# DIPSY_UL1K16_LED5.net
KiCad netlist of a schematic drawn in Altium Designer
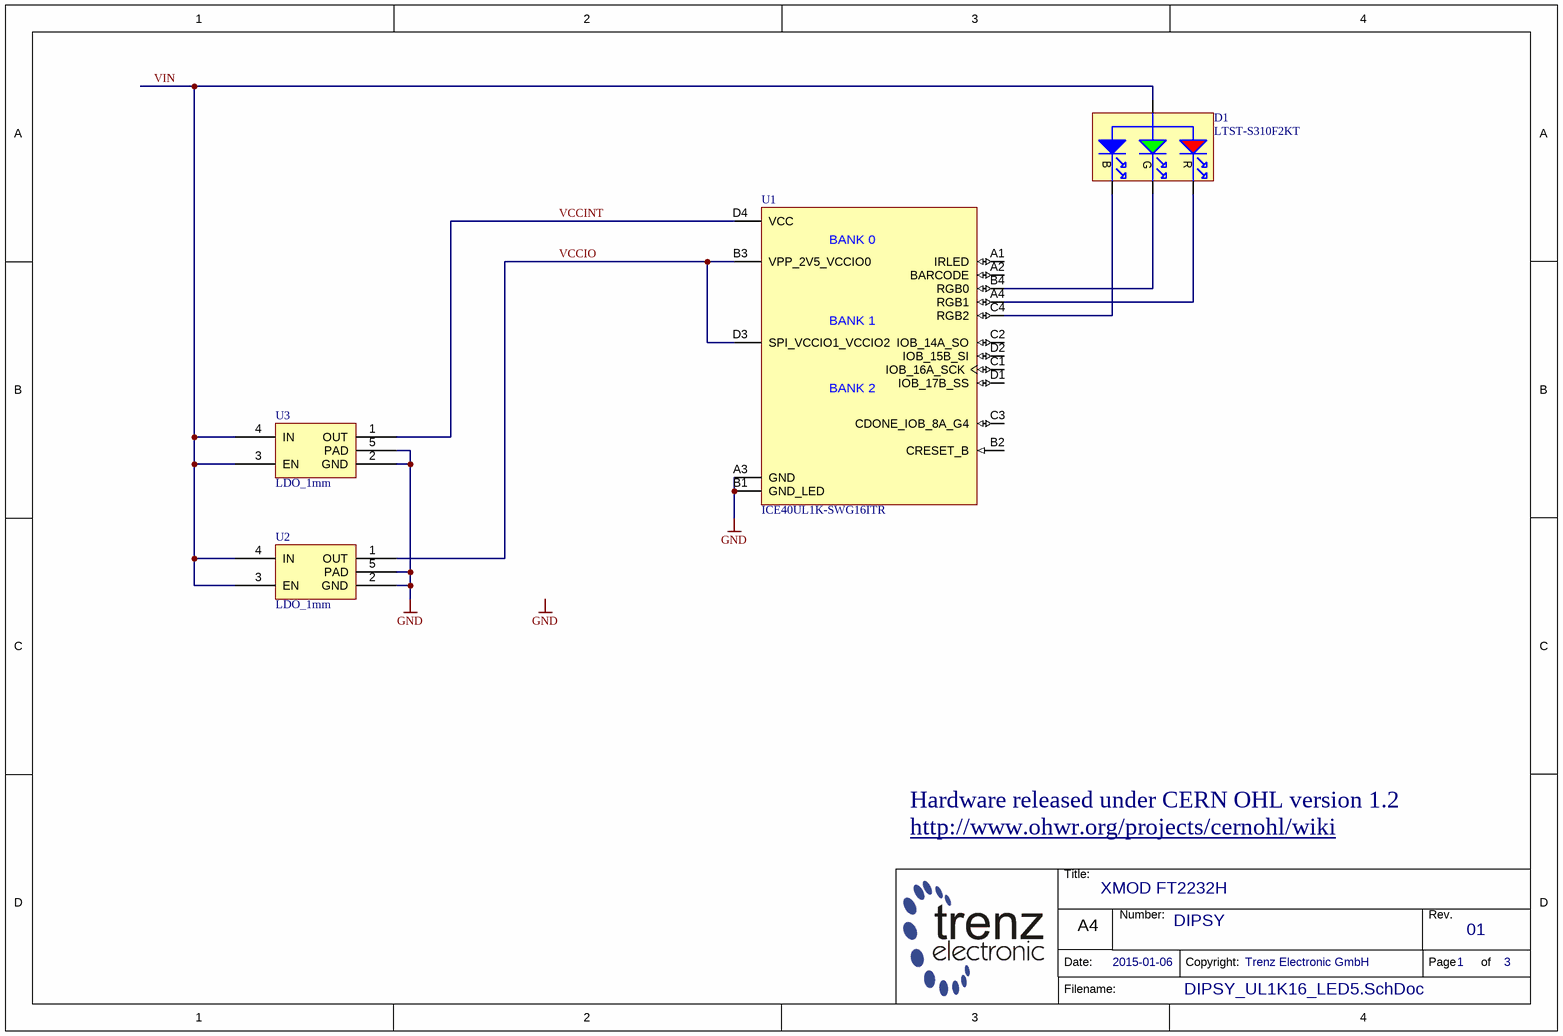
[diagram p0: DIPSY_UL1K16_LED5.SchDoc]

(export (version "E")
  (design (tool "Eeschema 10.0.6"))
  (components
    (comp (ref "D1")
      (value "LTST-S310F2KT")
      (footprint "LTST-S310F2KT")
      (libsource (lib "LTST-S310F2KT") (part "LTST-S310F2KT"))
    )
    (comp (ref "U1")
      (value "ICE40UL1K-SWG16ITR")
      (footprint "BGA16C35P4X4_140X140X49B21N")
      (libsource (lib "altium-import") (part "root_0_ICE40UL1K-SWG16ITR_"))
    )
    (comp (ref "U2")
      (value "LDO_1mm")
      (footprint "DFN65P100X45-4N")
      (libsource (lib "LDO_1mm") (part "LDO_1mm"))
    )
    (comp (ref "U3")
      (value "LDO_1mm")
      (footprint "DFN65P100X45-4N")
      (libsource (lib "LDO_1mm") (part "LDO_1mm"))
    )
  )
  (nets
    (net (code "1") (name "/VCCINT") (class "Default")
      (node (ref "U1") (pin "D4") (pinfunction "VCC_D4") (pintype "power_in"))
      (node (ref "U3") (pin "1") (pinfunction "OUT_1") (pintype "passive"))
    )
    (net (code "2") (name "/VCCIO") (class "Default")
      (node (ref "U1") (pin "B3") (pinfunction "VPP_2V5_VCCIO0_B3") (pintype "power_in"))
      (node (ref "U1") (pin "D3") (pinfunction "SPI_VCCIO1_VCCIO2_D3") (pintype "power_in"))
      (node (ref "U2") (pin "1") (pinfunction "OUT_1") (pintype "passive"))
    )
    (net (code "3") (name "/VIN") (class "Default")
      (node (ref "D1") (pin "4") (pinfunction "ANODE_4") (pintype "passive"))
      (node (ref "U2") (pin "3") (pinfunction "EN_3") (pintype "passive"))
      (node (ref "U2") (pin "4") (pinfunction "IN_4") (pintype "passive"))
      (node (ref "U3") (pin "3") (pinfunction "EN_3") (pintype "passive"))
      (node (ref "U3") (pin "4") (pinfunction "IN_4") (pintype "passive"))
    )
    (net (code "4") (name "GND") (class "Default")
      (node (ref "U1") (pin "A3") (pinfunction "GND_A3") (pintype "power_in"))
      (node (ref "U1") (pin "B1") (pinfunction "GND_LED_B1") (pintype "power_in"))
      (node (ref "U2") (pin "2") (pinfunction "GND_2") (pintype "passive"))
      (node (ref "U2") (pin "5") (pinfunction "PAD_5") (pintype "passive"))
      (node (ref "U3") (pin "2") (pinfunction "GND_2") (pintype "passive"))
      (node (ref "U3") (pin "5") (pinfunction "PAD_5") (pintype "passive"))
    )
    (net (code "5") (name "Net-(D1-BLUE)") (class "Default")
      (node (ref "D1") (pin "3") (pinfunction "BLUE_3") (pintype "passive"))
      (node (ref "U1") (pin "C4") (pinfunction "RGB2_C4") (pintype "bidirectional"))
    )
    (net (code "6") (name "Net-(D1-GREEN)") (class "Default")
      (node (ref "D1") (pin "2") (pinfunction "GREEN_2") (pintype "passive"))
      (node (ref "U1") (pin "B4") (pinfunction "RGB0_B4") (pintype "bidirectional"))
    )
    (net (code "7") (name "Net-(D1-RED)") (class "Default")
      (node (ref "D1") (pin "1") (pinfunction "RED_1") (pintype "passive"))
      (node (ref "U1") (pin "A4") (pinfunction "RGB1_A4") (pintype "bidirectional"))
    )
    (net (code "8") (name "unconnected-(U1-BARCODE-PadA2)") (class "Default")
      (node (ref "U1") (pin "A2") (pinfunction "BARCODE_A2") (pintype "bidirectional"))
    )
    (net (code "9") (name "unconnected-(U1-CDONE_IOB_8A_G4-PadC3)") (class "Default")
      (node (ref "U1") (pin "C3") (pinfunction "CDONE_IOB_8A_G4_C3") (pintype "bidirectional"))
    )
    (net (code "10") (name "unconnected-(U1-CRESET_B-PadB2)") (class "Default")
      (node (ref "U1") (pin "B2") (pinfunction "CRESET_B_B2") (pintype "input"))
    )
    (net (code "11") (name "unconnected-(U1-IOB_14A_SO-PadC2)") (class "Default")
      (node (ref "U1") (pin "C2") (pinfunction "IOB_14A_SO_C2") (pintype "bidirectional"))
    )
    (net (code "12") (name "unconnected-(U1-IOB_15B_SI-PadD2)") (class "Default")
      (node (ref "U1") (pin "D2") (pinfunction "IOB_15B_SI_D2") (pintype "bidirectional"))
    )
    (net (code "13") (name "unconnected-(U1-IOB_16A_SCK-PadC1)") (class "Default")
      (node (ref "U1") (pin "C1") (pinfunction "IOB_16A_SCK_C1") (pintype "bidirectional"))
    )
    (net (code "14") (name "unconnected-(U1-IOB_17B_SS-PadD1)") (class "Default")
      (node (ref "U1") (pin "D1") (pinfunction "IOB_17B_SS_D1") (pintype "bidirectional"))
    )
    (net (code "15") (name "unconnected-(U1-IRLED-PadA1)") (class "Default")
      (node (ref "U1") (pin "A1") (pinfunction "IRLED_A1") (pintype "bidirectional"))
    )
  )
)
